# SS_24.net
KiCad netlist of a schematic drawn in Altium Designer
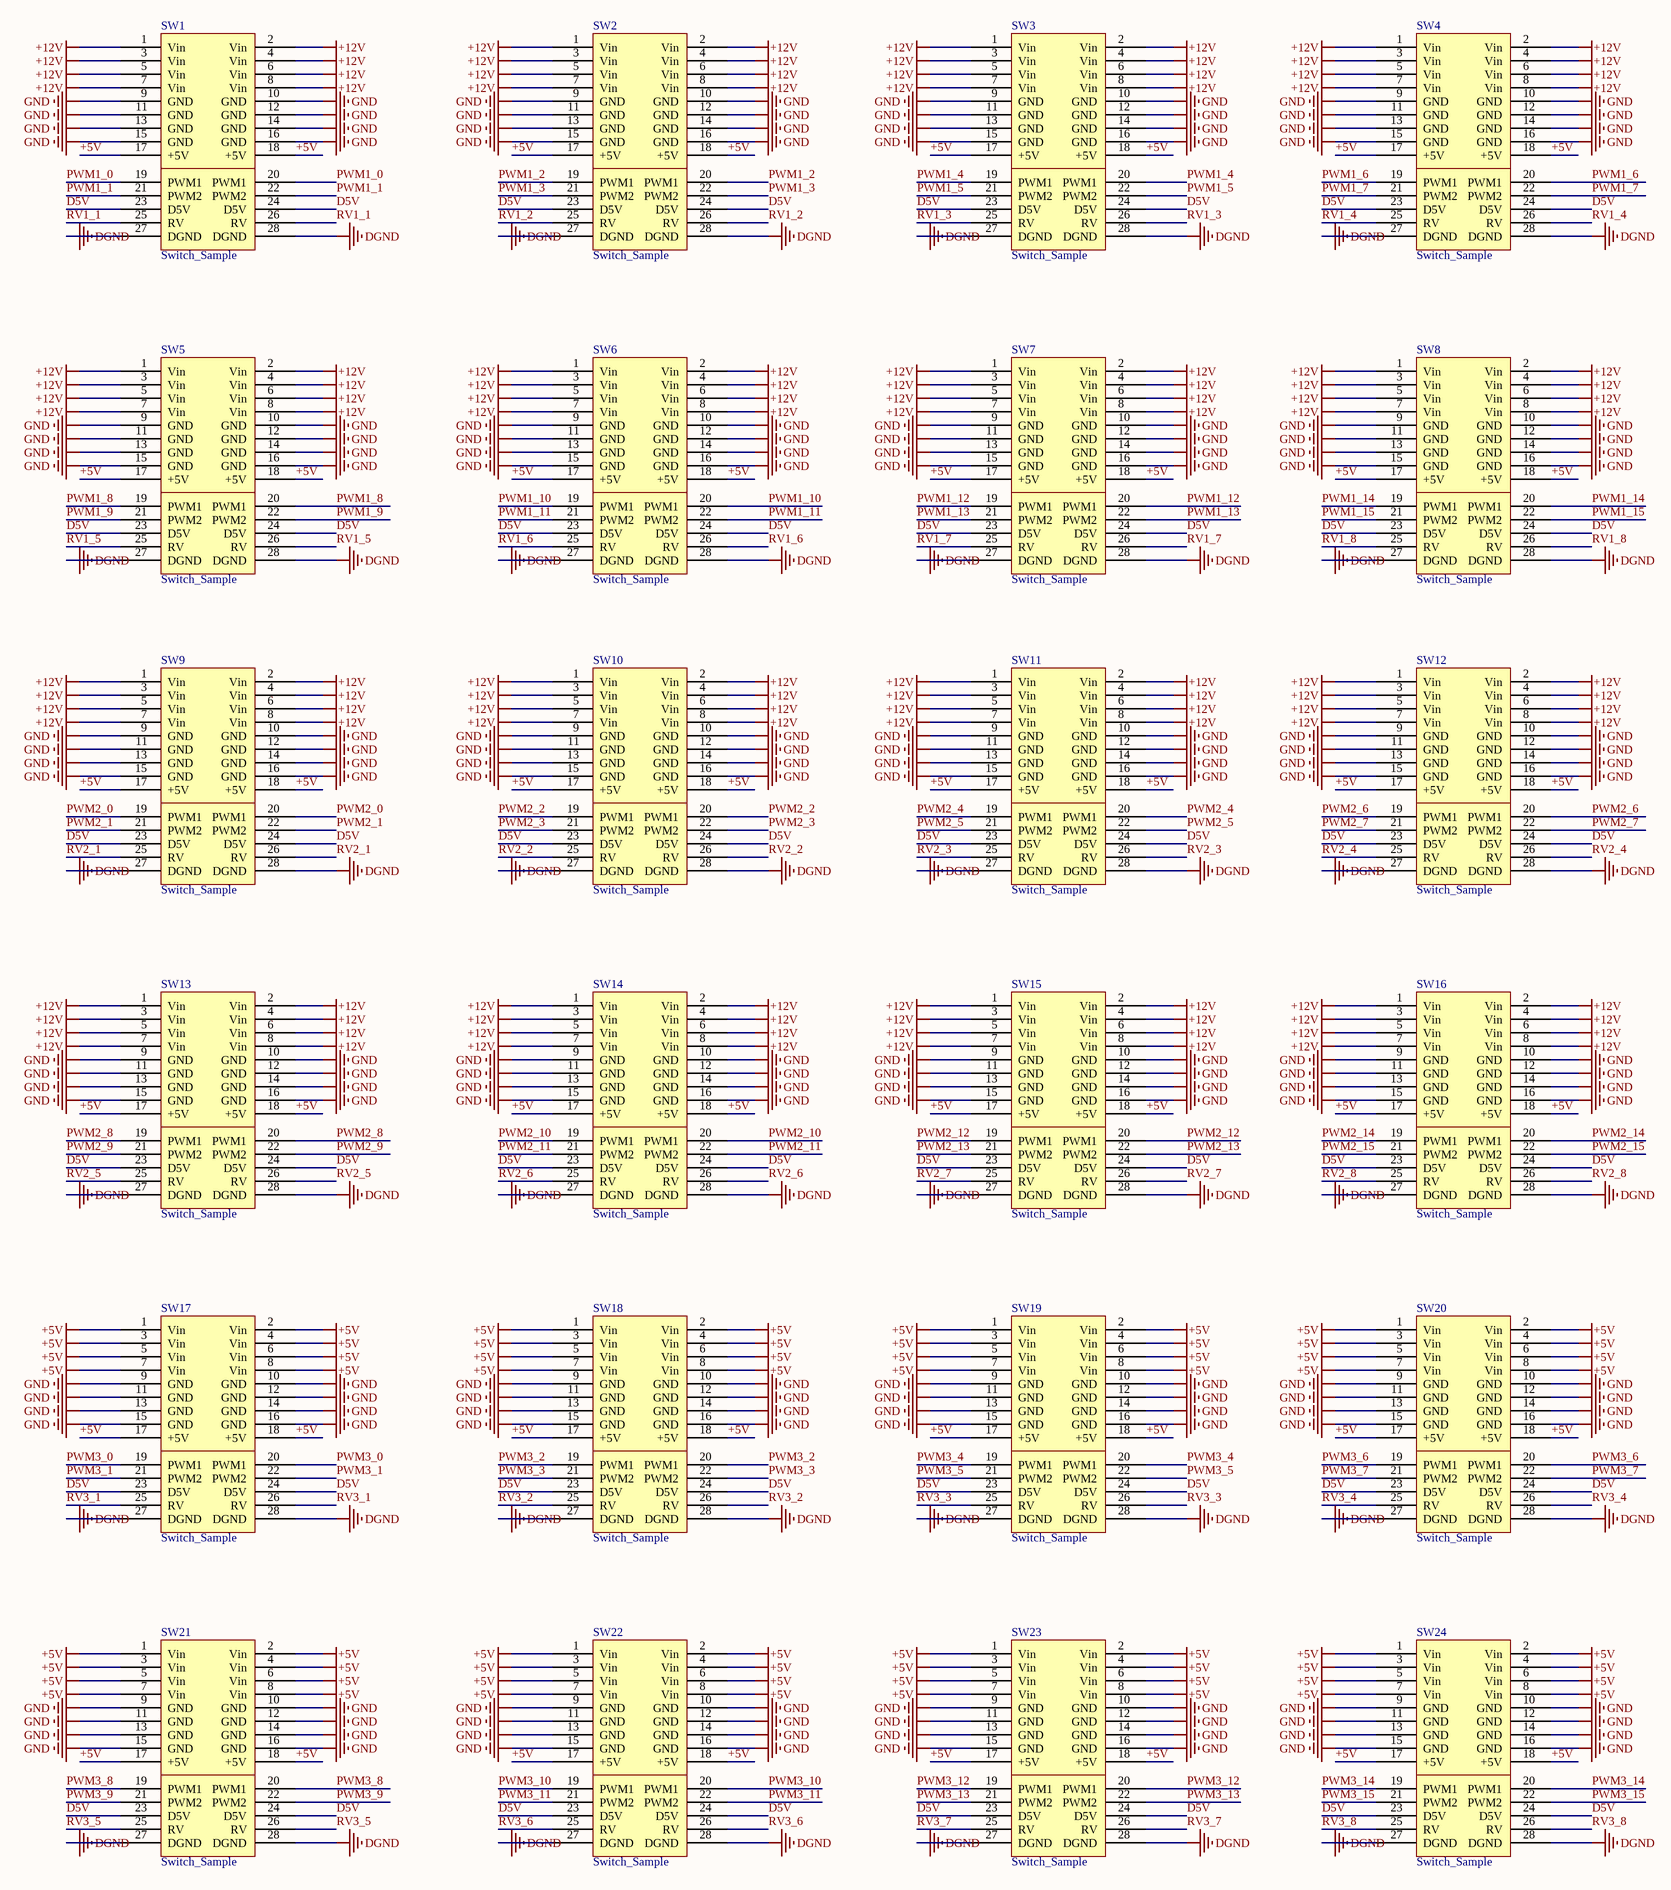
[diagram p0: SS_24.SchDoc]

(export (version "E")
  (design (tool "Eeschema 10.0.6"))
  (components
    (comp (ref "SW1")
      (value "Switch_Sample")
      (footprint "Switch_Sample")
      (libsource (lib "Schlib1") (part "Switch_Sample"))
    )
    (comp (ref "SW2")
      (value "Switch_Sample")
      (footprint "Switch_Sample")
      (libsource (lib "Schlib1") (part "Switch_Sample"))
    )
    (comp (ref "SW3")
      (value "Switch_Sample")
      (footprint "Switch_Sample")
      (libsource (lib "Schlib1") (part "Switch_Sample"))
    )
    (comp (ref "SW4")
      (value "Switch_Sample")
      (footprint "Switch_Sample")
      (libsource (lib "Schlib1") (part "Switch_Sample"))
    )
    (comp (ref "SW5")
      (value "Switch_Sample")
      (footprint "Switch_Sample")
      (libsource (lib "Schlib1") (part "Switch_Sample"))
    )
    (comp (ref "SW6")
      (value "Switch_Sample")
      (footprint "Switch_Sample")
      (libsource (lib "Schlib1") (part "Switch_Sample"))
    )
    (comp (ref "SW7")
      (value "Switch_Sample")
      (footprint "Switch_Sample")
      (libsource (lib "Schlib1") (part "Switch_Sample"))
    )
    (comp (ref "SW8")
      (value "Switch_Sample")
      (footprint "Switch_Sample")
      (libsource (lib "Schlib1") (part "Switch_Sample"))
    )
    (comp (ref "SW9")
      (value "Switch_Sample")
      (footprint "Switch_Sample")
      (libsource (lib "Schlib1") (part "Switch_Sample"))
    )
    (comp (ref "SW10")
      (value "Switch_Sample")
      (footprint "Switch_Sample")
      (libsource (lib "Schlib1") (part "Switch_Sample"))
    )
    (comp (ref "SW11")
      (value "Switch_Sample")
      (footprint "Switch_Sample")
      (libsource (lib "Schlib1") (part "Switch_Sample"))
    )
    (comp (ref "SW12")
      (value "Switch_Sample")
      (footprint "Switch_Sample")
      (libsource (lib "Schlib1") (part "Switch_Sample"))
    )
    (comp (ref "SW13")
      (value "Switch_Sample")
      (footprint "Switch_Sample")
      (libsource (lib "Schlib1") (part "Switch_Sample"))
    )
    (comp (ref "SW14")
      (value "Switch_Sample")
      (footprint "Switch_Sample")
      (libsource (lib "Schlib1") (part "Switch_Sample"))
    )
    (comp (ref "SW15")
      (value "Switch_Sample")
      (footprint "Switch_Sample")
      (libsource (lib "Schlib1") (part "Switch_Sample"))
    )
    (comp (ref "SW16")
      (value "Switch_Sample")
      (footprint "Switch_Sample")
      (libsource (lib "Schlib1") (part "Switch_Sample"))
    )
    (comp (ref "SW17")
      (value "Switch_Sample")
      (footprint "Switch_Sample")
      (libsource (lib "Schlib1") (part "Switch_Sample"))
    )
    (comp (ref "SW18")
      (value "Switch_Sample")
      (footprint "Switch_Sample")
      (libsource (lib "Schlib1") (part "Switch_Sample"))
    )
    (comp (ref "SW19")
      (value "Switch_Sample")
      (footprint "Switch_Sample")
      (libsource (lib "Schlib1") (part "Switch_Sample"))
    )
    (comp (ref "SW20")
      (value "Switch_Sample")
      (footprint "Switch_Sample")
      (libsource (lib "Schlib1") (part "Switch_Sample"))
    )
    (comp (ref "SW21")
      (value "Switch_Sample")
      (footprint "Switch_Sample")
      (libsource (lib "Schlib1") (part "Switch_Sample"))
    )
    (comp (ref "SW22")
      (value "Switch_Sample")
      (footprint "Switch_Sample")
      (libsource (lib "Schlib1") (part "Switch_Sample"))
    )
    (comp (ref "SW23")
      (value "Switch_Sample")
      (footprint "Switch_Sample")
      (libsource (lib "Schlib1") (part "Switch_Sample"))
    )
    (comp (ref "SW24")
      (value "Switch_Sample")
      (footprint "Switch_Sample")
      (libsource (lib "Schlib1") (part "Switch_Sample"))
    )
  )
  (nets
    (net (code "1") (name "+5V") (class "Default")
      (node (ref "SW1") (pin "17") (pinfunction "+5V_17") (pintype "passive"))
      (node (ref "SW1") (pin "18") (pinfunction "+5V_18") (pintype "passive"))
      (node (ref "SW10") (pin "17") (pinfunction "+5V_17") (pintype "passive"))
      (node (ref "SW10") (pin "18") (pinfunction "+5V_18") (pintype "passive"))
      (node (ref "SW11") (pin "17") (pinfunction "+5V_17") (pintype "passive"))
      (node (ref "SW11") (pin "18") (pinfunction "+5V_18") (pintype "passive"))
      (node (ref "SW12") (pin "17") (pinfunction "+5V_17") (pintype "passive"))
      (node (ref "SW12") (pin "18") (pinfunction "+5V_18") (pintype "passive"))
      (node (ref "SW13") (pin "17") (pinfunction "+5V_17") (pintype "passive"))
      (node (ref "SW13") (pin "18") (pinfunction "+5V_18") (pintype "passive"))
      (node (ref "SW14") (pin "17") (pinfunction "+5V_17") (pintype "passive"))
      (node (ref "SW14") (pin "18") (pinfunction "+5V_18") (pintype "passive"))
      (node (ref "SW15") (pin "17") (pinfunction "+5V_17") (pintype "passive"))
      (node (ref "SW15") (pin "18") (pinfunction "+5V_18") (pintype "passive"))
      (node (ref "SW16") (pin "17") (pinfunction "+5V_17") (pintype "passive"))
      (node (ref "SW16") (pin "18") (pinfunction "+5V_18") (pintype "passive"))
      (node (ref "SW17") (pin "1") (pinfunction "Vin_1") (pintype "passive"))
      (node (ref "SW17") (pin "17") (pinfunction "+5V_17") (pintype "passive"))
      (node (ref "SW17") (pin "18") (pinfunction "+5V_18") (pintype "passive"))
      (node (ref "SW17") (pin "2") (pinfunction "Vin_2") (pintype "passive"))
      (node (ref "SW17") (pin "3") (pinfunction "Vin_3") (pintype "passive"))
      (node (ref "SW17") (pin "4") (pinfunction "Vin_4") (pintype "passive"))
      (node (ref "SW17") (pin "5") (pinfunction "Vin_5") (pintype "passive"))
      (node (ref "SW17") (pin "6") (pinfunction "Vin_6") (pintype "passive"))
      (node (ref "SW17") (pin "7") (pinfunction "Vin_7") (pintype "passive"))
      (node (ref "SW17") (pin "8") (pinfunction "Vin_8") (pintype "passive"))
      (node (ref "SW18") (pin "1") (pinfunction "Vin_1") (pintype "passive"))
      (node (ref "SW18") (pin "17") (pinfunction "+5V_17") (pintype "passive"))
      (node (ref "SW18") (pin "18") (pinfunction "+5V_18") (pintype "passive"))
      (node (ref "SW18") (pin "2") (pinfunction "Vin_2") (pintype "passive"))
      (node (ref "SW18") (pin "3") (pinfunction "Vin_3") (pintype "passive"))
      (node (ref "SW18") (pin "4") (pinfunction "Vin_4") (pintype "passive"))
      (node (ref "SW18") (pin "5") (pinfunction "Vin_5") (pintype "passive"))
      (node (ref "SW18") (pin "6") (pinfunction "Vin_6") (pintype "passive"))
      (node (ref "SW18") (pin "7") (pinfunction "Vin_7") (pintype "passive"))
      (node (ref "SW18") (pin "8") (pinfunction "Vin_8") (pintype "passive"))
      (node (ref "SW19") (pin "1") (pinfunction "Vin_1") (pintype "passive"))
      (node (ref "SW19") (pin "17") (pinfunction "+5V_17") (pintype "passive"))
      (node (ref "SW19") (pin "18") (pinfunction "+5V_18") (pintype "passive"))
      (node (ref "SW19") (pin "2") (pinfunction "Vin_2") (pintype "passive"))
      (node (ref "SW19") (pin "3") (pinfunction "Vin_3") (pintype "passive"))
      (node (ref "SW19") (pin "4") (pinfunction "Vin_4") (pintype "passive"))
      (node (ref "SW19") (pin "5") (pinfunction "Vin_5") (pintype "passive"))
      (node (ref "SW19") (pin "6") (pinfunction "Vin_6") (pintype "passive"))
      (node (ref "SW19") (pin "7") (pinfunction "Vin_7") (pintype "passive"))
      (node (ref "SW19") (pin "8") (pinfunction "Vin_8") (pintype "passive"))
      (node (ref "SW2") (pin "17") (pinfunction "+5V_17") (pintype "passive"))
      (node (ref "SW2") (pin "18") (pinfunction "+5V_18") (pintype "passive"))
      (node (ref "SW20") (pin "1") (pinfunction "Vin_1") (pintype "passive"))
      (node (ref "SW20") (pin "17") (pinfunction "+5V_17") (pintype "passive"))
      (node (ref "SW20") (pin "18") (pinfunction "+5V_18") (pintype "passive"))
      (node (ref "SW20") (pin "2") (pinfunction "Vin_2") (pintype "passive"))
      (node (ref "SW20") (pin "3") (pinfunction "Vin_3") (pintype "passive"))
      (node (ref "SW20") (pin "4") (pinfunction "Vin_4") (pintype "passive"))
      (node (ref "SW20") (pin "5") (pinfunction "Vin_5") (pintype "passive"))
      (node (ref "SW20") (pin "6") (pinfunction "Vin_6") (pintype "passive"))
      (node (ref "SW20") (pin "7") (pinfunction "Vin_7") (pintype "passive"))
      (node (ref "SW20") (pin "8") (pinfunction "Vin_8") (pintype "passive"))
      (node (ref "SW21") (pin "1") (pinfunction "Vin_1") (pintype "passive"))
      (node (ref "SW21") (pin "17") (pinfunction "+5V_17") (pintype "passive"))
      (node (ref "SW21") (pin "18") (pinfunction "+5V_18") (pintype "passive"))
      (node (ref "SW21") (pin "2") (pinfunction "Vin_2") (pintype "passive"))
      (node (ref "SW21") (pin "3") (pinfunction "Vin_3") (pintype "passive"))
      (node (ref "SW21") (pin "4") (pinfunction "Vin_4") (pintype "passive"))
      (node (ref "SW21") (pin "5") (pinfunction "Vin_5") (pintype "passive"))
      (node (ref "SW21") (pin "6") (pinfunction "Vin_6") (pintype "passive"))
      (node (ref "SW21") (pin "7") (pinfunction "Vin_7") (pintype "passive"))
      (node (ref "SW21") (pin "8") (pinfunction "Vin_8") (pintype "passive"))
      (node (ref "SW22") (pin "1") (pinfunction "Vin_1") (pintype "passive"))
      (node (ref "SW22") (pin "17") (pinfunction "+5V_17") (pintype "passive"))
      (node (ref "SW22") (pin "18") (pinfunction "+5V_18") (pintype "passive"))
      (node (ref "SW22") (pin "2") (pinfunction "Vin_2") (pintype "passive"))
      (node (ref "SW22") (pin "3") (pinfunction "Vin_3") (pintype "passive"))
      (node (ref "SW22") (pin "4") (pinfunction "Vin_4") (pintype "passive"))
      (node (ref "SW22") (pin "5") (pinfunction "Vin_5") (pintype "passive"))
      (node (ref "SW22") (pin "6") (pinfunction "Vin_6") (pintype "passive"))
      (node (ref "SW22") (pin "7") (pinfunction "Vin_7") (pintype "passive"))
      (node (ref "SW22") (pin "8") (pinfunction "Vin_8") (pintype "passive"))
      (node (ref "SW23") (pin "1") (pinfunction "Vin_1") (pintype "passive"))
      (node (ref "SW23") (pin "17") (pinfunction "+5V_17") (pintype "passive"))
      (node (ref "SW23") (pin "18") (pinfunction "+5V_18") (pintype "passive"))
      (node (ref "SW23") (pin "2") (pinfunction "Vin_2") (pintype "passive"))
      (node (ref "SW23") (pin "3") (pinfunction "Vin_3") (pintype "passive"))
      (node (ref "SW23") (pin "4") (pinfunction "Vin_4") (pintype "passive"))
      (node (ref "SW23") (pin "5") (pinfunction "Vin_5") (pintype "passive"))
      (node (ref "SW23") (pin "6") (pinfunction "Vin_6") (pintype "passive"))
      (node (ref "SW23") (pin "7") (pinfunction "Vin_7") (pintype "passive"))
      (node (ref "SW23") (pin "8") (pinfunction "Vin_8") (pintype "passive"))
      (node (ref "SW24") (pin "1") (pinfunction "Vin_1") (pintype "passive"))
      (node (ref "SW24") (pin "17") (pinfunction "+5V_17") (pintype "passive"))
      (node (ref "SW24") (pin "18") (pinfunction "+5V_18") (pintype "passive"))
      (node (ref "SW24") (pin "2") (pinfunction "Vin_2") (pintype "passive"))
      (node (ref "SW24") (pin "3") (pinfunction "Vin_3") (pintype "passive"))
      (node (ref "SW24") (pin "4") (pinfunction "Vin_4") (pintype "passive"))
      (node (ref "SW24") (pin "5") (pinfunction "Vin_5") (pintype "passive"))
      (node (ref "SW24") (pin "6") (pinfunction "Vin_6") (pintype "passive"))
      (node (ref "SW24") (pin "7") (pinfunction "Vin_7") (pintype "passive"))
      (node (ref "SW24") (pin "8") (pinfunction "Vin_8") (pintype "passive"))
      (node (ref "SW3") (pin "17") (pinfunction "+5V_17") (pintype "passive"))
      (node (ref "SW3") (pin "18") (pinfunction "+5V_18") (pintype "passive"))
      (node (ref "SW4") (pin "17") (pinfunction "+5V_17") (pintype "passive"))
      (node (ref "SW4") (pin "18") (pinfunction "+5V_18") (pintype "passive"))
      (node (ref "SW5") (pin "17") (pinfunction "+5V_17") (pintype "passive"))
      (node (ref "SW5") (pin "18") (pinfunction "+5V_18") (pintype "passive"))
      (node (ref "SW6") (pin "17") (pinfunction "+5V_17") (pintype "passive"))
      (node (ref "SW6") (pin "18") (pinfunction "+5V_18") (pintype "passive"))
      (node (ref "SW7") (pin "17") (pinfunction "+5V_17") (pintype "passive"))
      (node (ref "SW7") (pin "18") (pinfunction "+5V_18") (pintype "passive"))
      (node (ref "SW8") (pin "17") (pinfunction "+5V_17") (pintype "passive"))
      (node (ref "SW8") (pin "18") (pinfunction "+5V_18") (pintype "passive"))
      (node (ref "SW9") (pin "17") (pinfunction "+5V_17") (pintype "passive"))
      (node (ref "SW9") (pin "18") (pinfunction "+5V_18") (pintype "passive"))
    )
    (net (code "2") (name "+12V") (class "Default")
      (node (ref "SW1") (pin "1") (pinfunction "Vin_1") (pintype "passive"))
      (node (ref "SW1") (pin "2") (pinfunction "Vin_2") (pintype "passive"))
      (node (ref "SW1") (pin "3") (pinfunction "Vin_3") (pintype "passive"))
      (node (ref "SW1") (pin "4") (pinfunction "Vin_4") (pintype "passive"))
      (node (ref "SW1") (pin "5") (pinfunction "Vin_5") (pintype "passive"))
      (node (ref "SW1") (pin "6") (pinfunction "Vin_6") (pintype "passive"))
      (node (ref "SW1") (pin "7") (pinfunction "Vin_7") (pintype "passive"))
      (node (ref "SW1") (pin "8") (pinfunction "Vin_8") (pintype "passive"))
      (node (ref "SW10") (pin "1") (pinfunction "Vin_1") (pintype "passive"))
      (node (ref "SW10") (pin "2") (pinfunction "Vin_2") (pintype "passive"))
      (node (ref "SW10") (pin "3") (pinfunction "Vin_3") (pintype "passive"))
      (node (ref "SW10") (pin "4") (pinfunction "Vin_4") (pintype "passive"))
      (node (ref "SW10") (pin "5") (pinfunction "Vin_5") (pintype "passive"))
      (node (ref "SW10") (pin "6") (pinfunction "Vin_6") (pintype "passive"))
      (node (ref "SW10") (pin "7") (pinfunction "Vin_7") (pintype "passive"))
      (node (ref "SW10") (pin "8") (pinfunction "Vin_8") (pintype "passive"))
      (node (ref "SW11") (pin "1") (pinfunction "Vin_1") (pintype "passive"))
      (node (ref "SW11") (pin "2") (pinfunction "Vin_2") (pintype "passive"))
      (node (ref "SW11") (pin "3") (pinfunction "Vin_3") (pintype "passive"))
      (node (ref "SW11") (pin "4") (pinfunction "Vin_4") (pintype "passive"))
      (node (ref "SW11") (pin "5") (pinfunction "Vin_5") (pintype "passive"))
      (node (ref "SW11") (pin "6") (pinfunction "Vin_6") (pintype "passive"))
      (node (ref "SW11") (pin "7") (pinfunction "Vin_7") (pintype "passive"))
      (node (ref "SW11") (pin "8") (pinfunction "Vin_8") (pintype "passive"))
      (node (ref "SW12") (pin "1") (pinfunction "Vin_1") (pintype "passive"))
      (node (ref "SW12") (pin "2") (pinfunction "Vin_2") (pintype "passive"))
      (node (ref "SW12") (pin "3") (pinfunction "Vin_3") (pintype "passive"))
      (node (ref "SW12") (pin "4") (pinfunction "Vin_4") (pintype "passive"))
      (node (ref "SW12") (pin "5") (pinfunction "Vin_5") (pintype "passive"))
      (node (ref "SW12") (pin "6") (pinfunction "Vin_6") (pintype "passive"))
      (node (ref "SW12") (pin "7") (pinfunction "Vin_7") (pintype "passive"))
      (node (ref "SW12") (pin "8") (pinfunction "Vin_8") (pintype "passive"))
      (node (ref "SW13") (pin "1") (pinfunction "Vin_1") (pintype "passive"))
      (node (ref "SW13") (pin "2") (pinfunction "Vin_2") (pintype "passive"))
      (node (ref "SW13") (pin "3") (pinfunction "Vin_3") (pintype "passive"))
      (node (ref "SW13") (pin "4") (pinfunction "Vin_4") (pintype "passive"))
      (node (ref "SW13") (pin "5") (pinfunction "Vin_5") (pintype "passive"))
      (node (ref "SW13") (pin "6") (pinfunction "Vin_6") (pintype "passive"))
      (node (ref "SW13") (pin "7") (pinfunction "Vin_7") (pintype "passive"))
      (node (ref "SW13") (pin "8") (pinfunction "Vin_8") (pintype "passive"))
      (node (ref "SW14") (pin "1") (pinfunction "Vin_1") (pintype "passive"))
      (node (ref "SW14") (pin "2") (pinfunction "Vin_2") (pintype "passive"))
      (node (ref "SW14") (pin "3") (pinfunction "Vin_3") (pintype "passive"))
      (node (ref "SW14") (pin "4") (pinfunction "Vin_4") (pintype "passive"))
      (node (ref "SW14") (pin "5") (pinfunction "Vin_5") (pintype "passive"))
      (node (ref "SW14") (pin "6") (pinfunction "Vin_6") (pintype "passive"))
      (node (ref "SW14") (pin "7") (pinfunction "Vin_7") (pintype "passive"))
      (node (ref "SW14") (pin "8") (pinfunction "Vin_8") (pintype "passive"))
      (node (ref "SW15") (pin "1") (pinfunction "Vin_1") (pintype "passive"))
      (node (ref "SW15") (pin "2") (pinfunction "Vin_2") (pintype "passive"))
      (node (ref "SW15") (pin "3") (pinfunction "Vin_3") (pintype "passive"))
      (node (ref "SW15") (pin "4") (pinfunction "Vin_4") (pintype "passive"))
      (node (ref "SW15") (pin "5") (pinfunction "Vin_5") (pintype "passive"))
      (node (ref "SW15") (pin "6") (pinfunction "Vin_6") (pintype "passive"))
      (node (ref "SW15") (pin "7") (pinfunction "Vin_7") (pintype "passive"))
      (node (ref "SW15") (pin "8") (pinfunction "Vin_8") (pintype "passive"))
      (node (ref "SW16") (pin "1") (pinfunction "Vin_1") (pintype "passive"))
      (node (ref "SW16") (pin "2") (pinfunction "Vin_2") (pintype "passive"))
      (node (ref "SW16") (pin "3") (pinfunction "Vin_3") (pintype "passive"))
      (node (ref "SW16") (pin "4") (pinfunction "Vin_4") (pintype "passive"))
      (node (ref "SW16") (pin "5") (pinfunction "Vin_5") (pintype "passive"))
      (node (ref "SW16") (pin "6") (pinfunction "Vin_6") (pintype "passive"))
      (node (ref "SW16") (pin "7") (pinfunction "Vin_7") (pintype "passive"))
      (node (ref "SW16") (pin "8") (pinfunction "Vin_8") (pintype "passive"))
      (node (ref "SW2") (pin "1") (pinfunction "Vin_1") (pintype "passive"))
      (node (ref "SW2") (pin "2") (pinfunction "Vin_2") (pintype "passive"))
      (node (ref "SW2") (pin "3") (pinfunction "Vin_3") (pintype "passive"))
      (node (ref "SW2") (pin "4") (pinfunction "Vin_4") (pintype "passive"))
      (node (ref "SW2") (pin "5") (pinfunction "Vin_5") (pintype "passive"))
      (node (ref "SW2") (pin "6") (pinfunction "Vin_6") (pintype "passive"))
      (node (ref "SW2") (pin "7") (pinfunction "Vin_7") (pintype "passive"))
      (node (ref "SW2") (pin "8") (pinfunction "Vin_8") (pintype "passive"))
      (node (ref "SW3") (pin "1") (pinfunction "Vin_1") (pintype "passive"))
      (node (ref "SW3") (pin "2") (pinfunction "Vin_2") (pintype "passive"))
      (node (ref "SW3") (pin "3") (pinfunction "Vin_3") (pintype "passive"))
      (node (ref "SW3") (pin "4") (pinfunction "Vin_4") (pintype "passive"))
      (node (ref "SW3") (pin "5") (pinfunction "Vin_5") (pintype "passive"))
      (node (ref "SW3") (pin "6") (pinfunction "Vin_6") (pintype "passive"))
      (node (ref "SW3") (pin "7") (pinfunction "Vin_7") (pintype "passive"))
      (node (ref "SW3") (pin "8") (pinfunction "Vin_8") (pintype "passive"))
      (node (ref "SW4") (pin "1") (pinfunction "Vin_1") (pintype "passive"))
      (node (ref "SW4") (pin "2") (pinfunction "Vin_2") (pintype "passive"))
      (node (ref "SW4") (pin "3") (pinfunction "Vin_3") (pintype "passive"))
      (node (ref "SW4") (pin "4") (pinfunction "Vin_4") (pintype "passive"))
      (node (ref "SW4") (pin "5") (pinfunction "Vin_5") (pintype "passive"))
      (node (ref "SW4") (pin "6") (pinfunction "Vin_6") (pintype "passive"))
      (node (ref "SW4") (pin "7") (pinfunction "Vin_7") (pintype "passive"))
      (node (ref "SW4") (pin "8") (pinfunction "Vin_8") (pintype "passive"))
      (node (ref "SW5") (pin "1") (pinfunction "Vin_1") (pintype "passive"))
      (node (ref "SW5") (pin "2") (pinfunction "Vin_2") (pintype "passive"))
      (node (ref "SW5") (pin "3") (pinfunction "Vin_3") (pintype "passive"))
      (node (ref "SW5") (pin "4") (pinfunction "Vin_4") (pintype "passive"))
      (node (ref "SW5") (pin "5") (pinfunction "Vin_5") (pintype "passive"))
      (node (ref "SW5") (pin "6") (pinfunction "Vin_6") (pintype "passive"))
      (node (ref "SW5") (pin "7") (pinfunction "Vin_7") (pintype "passive"))
      (node (ref "SW5") (pin "8") (pinfunction "Vin_8") (pintype "passive"))
      (node (ref "SW6") (pin "1") (pinfunction "Vin_1") (pintype "passive"))
      (node (ref "SW6") (pin "2") (pinfunction "Vin_2") (pintype "passive"))
      (node (ref "SW6") (pin "3") (pinfunction "Vin_3") (pintype "passive"))
      (node (ref "SW6") (pin "4") (pinfunction "Vin_4") (pintype "passive"))
      (node (ref "SW6") (pin "5") (pinfunction "Vin_5") (pintype "passive"))
      (node (ref "SW6") (pin "6") (pinfunction "Vin_6") (pintype "passive"))
      (node (ref "SW6") (pin "7") (pinfunction "Vin_7") (pintype "passive"))
      (node (ref "SW6") (pin "8") (pinfunction "Vin_8") (pintype "passive"))
      (node (ref "SW7") (pin "1") (pinfunction "Vin_1") (pintype "passive"))
      (node (ref "SW7") (pin "2") (pinfunction "Vin_2") (pintype "passive"))
      (node (ref "SW7") (pin "3") (pinfunction "Vin_3") (pintype "passive"))
      (node (ref "SW7") (pin "4") (pinfunction "Vin_4") (pintype "passive"))
      (node (ref "SW7") (pin "5") (pinfunction "Vin_5") (pintype "passive"))
      (node (ref "SW7") (pin "6") (pinfunction "Vin_6") (pintype "passive"))
      (node (ref "SW7") (pin "7") (pinfunction "Vin_7") (pintype "passive"))
      (node (ref "SW7") (pin "8") (pinfunction "Vin_8") (pintype "passive"))
      (node (ref "SW8") (pin "1") (pinfunction "Vin_1") (pintype "passive"))
      (node (ref "SW8") (pin "2") (pinfunction "Vin_2") (pintype "passive"))
      (node (ref "SW8") (pin "3") (pinfunction "Vin_3") (pintype "passive"))
      (node (ref "SW8") (pin "4") (pinfunction "Vin_4") (pintype "passive"))
      (node (ref "SW8") (pin "5") (pinfunction "Vin_5") (pintype "passive"))
      (node (ref "SW8") (pin "6") (pinfunction "Vin_6") (pintype "passive"))
      (node (ref "SW8") (pin "7") (pinfunction "Vin_7") (pintype "passive"))
      (node (ref "SW8") (pin "8") (pinfunction "Vin_8") (pintype "passive"))
      (node (ref "SW9") (pin "1") (pinfunction "Vin_1") (pintype "passive"))
      (node (ref "SW9") (pin "2") (pinfunction "Vin_2") (pintype "passive"))
      (node (ref "SW9") (pin "3") (pinfunction "Vin_3") (pintype "passive"))
      (node (ref "SW9") (pin "4") (pinfunction "Vin_4") (pintype "passive"))
      (node (ref "SW9") (pin "5") (pinfunction "Vin_5") (pintype "passive"))
      (node (ref "SW9") (pin "6") (pinfunction "Vin_6") (pintype "passive"))
      (node (ref "SW9") (pin "7") (pinfunction "Vin_7") (pintype "passive"))
      (node (ref "SW9") (pin "8") (pinfunction "Vin_8") (pintype "passive"))
    )
    (net (code "3") (name "/D5V") (class "Default")
      (node (ref "SW1") (pin "23") (pinfunction "D5V_23") (pintype "passive"))
      (node (ref "SW1") (pin "24") (pinfunction "D5V_24") (pintype "passive"))
      (node (ref "SW10") (pin "23") (pinfunction "D5V_23") (pintype "passive"))
      (node (ref "SW10") (pin "24") (pinfunction "D5V_24") (pintype "passive"))
      (node (ref "SW11") (pin "23") (pinfunction "D5V_23") (pintype "passive"))
      (node (ref "SW11") (pin "24") (pinfunction "D5V_24") (pintype "passive"))
      (node (ref "SW12") (pin "23") (pinfunction "D5V_23") (pintype "passive"))
      (node (ref "SW12") (pin "24") (pinfunction "D5V_24") (pintype "passive"))
      (node (ref "SW13") (pin "23") (pinfunction "D5V_23") (pintype "passive"))
      (node (ref "SW13") (pin "24") (pinfunction "D5V_24") (pintype "passive"))
      (node (ref "SW14") (pin "23") (pinfunction "D5V_23") (pintype "passive"))
      (node (ref "SW14") (pin "24") (pinfunction "D5V_24") (pintype "passive"))
      (node (ref "SW15") (pin "23") (pinfunction "D5V_23") (pintype "passive"))
      (node (ref "SW15") (pin "24") (pinfunction "D5V_24") (pintype "passive"))
      (node (ref "SW16") (pin "23") (pinfunction "D5V_23") (pintype "passive"))
      (node (ref "SW16") (pin "24") (pinfunction "D5V_24") (pintype "passive"))
      (node (ref "SW17") (pin "23") (pinfunction "D5V_23") (pintype "passive"))
      (node (ref "SW17") (pin "24") (pinfunction "D5V_24") (pintype "passive"))
      (node (ref "SW18") (pin "23") (pinfunction "D5V_23") (pintype "passive"))
      (node (ref "SW18") (pin "24") (pinfunction "D5V_24") (pintype "passive"))
      (node (ref "SW19") (pin "23") (pinfunction "D5V_23") (pintype "passive"))
      (node (ref "SW19") (pin "24") (pinfunction "D5V_24") (pintype "passive"))
      (node (ref "SW2") (pin "23") (pinfunction "D5V_23") (pintype "passive"))
      (node (ref "SW2") (pin "24") (pinfunction "D5V_24") (pintype "passive"))
      (node (ref "SW20") (pin "23") (pinfunction "D5V_23") (pintype "passive"))
      (node (ref "SW20") (pin "24") (pinfunction "D5V_24") (pintype "passive"))
      (node (ref "SW21") (pin "23") (pinfunction "D5V_23") (pintype "passive"))
      (node (ref "SW21") (pin "24") (pinfunction "D5V_24") (pintype "passive"))
      (node (ref "SW22") (pin "23") (pinfunction "D5V_23") (pintype "passive"))
      (node (ref "SW22") (pin "24") (pinfunction "D5V_24") (pintype "passive"))
      (node (ref "SW23") (pin "23") (pinfunction "D5V_23") (pintype "passive"))
      (node (ref "SW23") (pin "24") (pinfunction "D5V_24") (pintype "passive"))
      (node (ref "SW24") (pin "23") (pinfunction "D5V_23") (pintype "passive"))
      (node (ref "SW24") (pin "24") (pinfunction "D5V_24") (pintype "passive"))
      (node (ref "SW3") (pin "23") (pinfunction "D5V_23") (pintype "passive"))
      (node (ref "SW3") (pin "24") (pinfunction "D5V_24") (pintype "passive"))
      (node (ref "SW4") (pin "23") (pinfunction "D5V_23") (pintype "passive"))
      (node (ref "SW4") (pin "24") (pinfunction "D5V_24") (pintype "passive"))
      (node (ref "SW5") (pin "23") (pinfunction "D5V_23") (pintype "passive"))
      (node (ref "SW5") (pin "24") (pinfunction "D5V_24") (pintype "passive"))
      (node (ref "SW6") (pin "23") (pinfunction "D5V_23") (pintype "passive"))
      (node (ref "SW6") (pin "24") (pinfunction "D5V_24") (pintype "passive"))
      (node (ref "SW7") (pin "23") (pinfunction "D5V_23") (pintype "passive"))
      (node (ref "SW7") (pin "24") (pinfunction "D5V_24") (pintype "passive"))
      (node (ref "SW8") (pin "23") (pinfunction "D5V_23") (pintype "passive"))
      (node (ref "SW8") (pin "24") (pinfunction "D5V_24") (pintype "passive"))
      (node (ref "SW9") (pin "23") (pinfunction "D5V_23") (pintype "passive"))
      (node (ref "SW9") (pin "24") (pinfunction "D5V_24") (pintype "passive"))
    )
    (net (code "4") (name "/PWM1_0") (class "Default")
      (node (ref "SW1") (pin "19") (pinfunction "PWM1_19") (pintype "passive"))
      (node (ref "SW1") (pin "20") (pinfunction "PWM1_20") (pintype "passive"))
    )
    (net (code "5") (name "/PWM1_1") (class "Default")
      (node (ref "SW1") (pin "21") (pinfunction "PWM2_21") (pintype "passive"))
      (node (ref "SW1") (pin "22") (pinfunction "PWM2_22") (pintype "passive"))
    )
    (net (code "6") (name "/PWM1_2") (class "Default")
      (node (ref "SW2") (pin "19") (pinfunction "PWM1_19") (pintype "passive"))
      (node (ref "SW2") (pin "20") (pinfunction "PWM1_20") (pintype "passive"))
    )
    (net (code "7") (name "/PWM1_3") (class "Default")
      (node (ref "SW2") (pin "21") (pinfunction "PWM2_21") (pintype "passive"))
      (node (ref "SW2") (pin "22") (pinfunction "PWM2_22") (pintype "passive"))
    )
    (net (code "8") (name "/PWM1_4") (class "Default")
      (node (ref "SW3") (pin "19") (pinfunction "PWM1_19") (pintype "passive"))
      (node (ref "SW3") (pin "20") (pinfunction "PWM1_20") (pintype "passive"))
    )
    (net (code "9") (name "/PWM1_5") (class "Default")
      (node (ref "SW3") (pin "21") (pinfunction "PWM2_21") (pintype "passive"))
      (node (ref "SW3") (pin "22") (pinfunction "PWM2_22") (pintype "passive"))
    )
    (net (code "10") (name "/PWM1_6") (class "Default")
      (node (ref "SW4") (pin "19") (pinfunction "PWM1_19") (pintype "passive"))
      (node (ref "SW4") (pin "20") (pinfunction "PWM1_20") (pintype "passive"))
    )
    (net (code "11") (name "/PWM1_7") (class "Default")
      (node (ref "SW4") (pin "21") (pinfunction "PWM2_21") (pintype "passive"))
      (node (ref "SW4") (pin "22") (pinfunction "PWM2_22") (pintype "passive"))
    )
    (net (code "12") (name "/PWM1_8") (class "Default")
      (node (ref "SW5") (pin "19") (pinfunction "PWM1_19") (pintype "passive"))
      (node (ref "SW5") (pin "20") (pinfunction "PWM1_20") (pintype "passive"))
    )
    (net (code "13") (name "/PWM1_9") (class "Default")
      (node (ref "SW5") (pin "21") (pinfunction "PWM2_21") (pintype "passive"))
      (node (ref "SW5") (pin "22") (pinfunction "PWM2_22") (pintype "passive"))
    )
    (net (code "14") (name "/PWM1_10") (class "Default")
      (node (ref "SW6") (pin "19") (pinfunction "PWM1_19") (pintype "passive"))
      (node (ref "SW6") (pin "20") (pinfunction "PWM1_20") (pintype "passive"))
    )
    (net (code "15") (name "/PWM1_11") (class "Default")
      (node (ref "SW6") (pin "21") (pinfunction "PWM2_21") (pintype "passive"))
      (node (ref "SW6") (pin "22") (pinfunction "PWM2_22") (pintype "passive"))
    )
    (net (code "16") (name "/PWM1_12") (class "Default")
      (node (ref "SW7") (pin "19") (pinfunction "PWM1_19") (pintype "passive"))
      (node (ref "SW7") (pin "20") (pinfunction "PWM1_20") (pintype "passive"))
    )
    (net (code "17") (name "/PWM1_13") (class "Default")
      (node (ref "SW7") (pin "21") (pinfunction "PWM2_21") (pintype "passive"))
      (node (ref "SW7") (pin "22") (pinfunction "PWM2_22") (pintype "passive"))
    )
    (net (code "18") (name "/PWM1_14") (class "Default")
      (node (ref "SW8") (pin "19") (pinfunction "PWM1_19") (pintype "passive"))
      (node (ref "SW8") (pin "20") (pinfunction "PWM1_20") (pintype "passive"))
    )
    (net (code "19") (name "/PWM1_15") (class "Default")
      (node (ref "SW8") (pin "21") (pinfunction "PWM2_21") (pintype "passive"))
      (node (ref "SW8") (pin "22") (pinfunction "PWM2_22") (pintype "passive"))
    )
    (net (code "20") (name "/PWM2_0") (class "Default")
      (node (ref "SW9") (pin "19") (pinfunction "PWM1_19") (pintype "passive"))
      (node (ref "SW9") (pin "20") (pinfunction "PWM1_20") (pintype "passive"))
    )
    (net (code "21") (name "/PWM2_1") (class "Default")
      (node (ref "SW9") (pin "21") (pinfunction "PWM2_21") (pintype "passive"))
      (node (ref "SW9") (pin "22") (pinfunction "PWM2_22") (pintype "passive"))
    )
    (net (code "22") (name "/PWM2_2") (class "Default")
      (node (ref "SW10") (pin "19") (pinfunction "PWM1_19") (pintype "passive"))
      (node (ref "SW10") (pin "20") (pinfunction "PWM1_20") (pintype "passive"))
    )
    (net (code "23") (name "/PWM2_3") (class "Default")
      (node (ref "SW10") (pin "21") (pinfunction "PWM2_21") (pintype "passive"))
      (node (ref "SW10") (pin "22") (pinfunction "PWM2_22") (pintype "passive"))
    )
    (net (code "24") (name "/PWM2_4") (class "Default")
      (node (ref "SW11") (pin "19") (pinfunction "PWM1_19") (pintype "passive"))
      (node (ref "SW11") (pin "20") (pinfunction "PWM1_20") (pintype "passive"))
    )
    (net (code "25") (name "/PWM2_5") (class "Default")
      (node (ref "SW11") (pin "21") (pinfunction "PWM2_21") (pintype "passive"))
      (node (ref "SW11") (pin "22") (pinfunction "PWM2_22") (pintype "passive"))
    )
    (net (code "26") (name "/PWM2_6") (class "Default")
      (node (ref "SW12") (pin "19") (pinfunction "PWM1_19") (pintype "passive"))
      (node (ref "SW12") (pin "20") (pinfunction "PWM1_20") (pintype "passive"))
    )
    (net (code "27") (name "/PWM2_7") (class "Default")
      (node (ref "SW12") (pin "21") (pinfunction "PWM2_21") (pintype "passive"))
      (node (ref "SW12") (pin "22") (pinfunction "PWM2_22") (pintype "passive"))
    )
    (net (code "28") (name "/PWM2_8") (class "Default")
      (node (ref "SW13") (pin "19") (pinfunction "PWM1_19") (pintype "passive"))
      (node (ref "SW13") (pin "20") (pinfunction "PWM1_20") (pintype "passive"))
    )
    (net (code "29") (name "/PWM2_9") (class "Default")
      (node (ref "SW13") (pin "21") (pinfunction "PWM2_21") (pintype "passive"))
      (node (ref "SW13") (pin "22") (pinfunction "PWM2_22") (pintype "passive"))
    )
    (net (code "30") (name "/PWM2_10") (class "Default")
      (node (ref "SW14") (pin "19") (pinfunction "PWM1_19") (pintype "passive"))
      (node (ref "SW14") (pin "20") (pinfunction "PWM1_20") (pintype "passive"))
    )
    (net (code "31") (name "/PWM2_11") (class "Default")
      (node (ref "SW14") (pin "21") (pinfunction "PWM2_21") (pintype "passive"))
      (node (ref "SW14") (pin "22") (pinfunction "PWM2_22") (pintype "passive"))
    )
    (net (code "32") (name "/PWM2_12") (class "Default")
      (node (ref "SW15") (pin "19") (pinfunction "PWM1_19") (pintype "passive"))
      (node (ref "SW15") (pin "20") (pinfunction "PWM1_20") (pintype "passive"))
    )
    (net (code "33") (name "/PWM2_13") (class "Default")
      (node (ref "SW15") (pin "21") (pinfunction "PWM2_21") (pintype "passive"))
      (node (ref "SW15") (pin "22") (pinfunction "PWM2_22") (pintype "passive"))
    )
    (net (code "34") (name "/PWM2_14") (class "Default")
      (node (ref "SW16") (pin "19") (pinfunction "PWM1_19") (pintype "passive"))
      (node (ref "SW16") (pin "20") (pinfunction "PWM1_20") (pintype "passive"))
    )
    (net (code "35") (name "/PWM2_15") (class "Default")
      (node (ref "SW16") (pin "21") (pinfunction "PWM2_21") (pintype "passive"))
      (node (ref "SW16") (pin "22") (pinfunction "PWM2_22") (pintype "passive"))
    )
    (net (code "36") (name "/PWM3_0") (class "Default")
      (node (ref "SW17") (pin "19") (pinfunction "PWM1_19") (pintype "passive"))
      (node (ref "SW17") (pin "20") (pinfunction "PWM1_20") (pintype "passive"))
    )
    (net (code "37") (name "/PWM3_1") (class "Default")
      (node (ref "SW17") (pin "21") (pinfunction "PWM2_21") (pintype "passive"))
      (node (ref "SW17") (pin "22") (pinfunction "PWM2_22") (pintype "passive"))
    )
    (net (code "38") (name "/PWM3_2") (class "Default")
      (node (ref "SW18") (pin "19") (pinfunction "PWM1_19") (pintype "passive"))
      (node (ref "SW18") (pin "20") (pinfunction "PWM1_20") (pintype "passive"))
    )
    (net (code "39") (name "/PWM3_3") (class "Default")
      (node (ref "SW18") (pin "21") (pinfunction "PWM2_21") (pintype "passive"))
      (node (ref "SW18") (pin "22") (pinfunction "PWM2_22") (pintype "passive"))
    )
    (net (code "40") (name "/PWM3_4") (class "Default")
      (node (ref "SW19") (pin "19") (pinfunction "PWM1_19") (pintype "passive"))
      (node (ref "SW19") (pin "20") (pinfunction "PWM1_20") (pintype "passive"))
    )
    (net (code "41") (name "/PWM3_5") (class "Default")
      (node (ref "SW19") (pin "21") (pinfunction "PWM2_21") (pintype "passive"))
      (node (ref "SW19") (pin "22") (pinfunction "PWM2_22") (pintype "passive"))
    )
    (net (code "42") (name "/PWM3_6") (class "Default")
      (node (ref "SW20") (pin "19") (pinfunction "PWM1_19") (pintype "passive"))
      (node (ref "SW20") (pin "20") (pinfunction "PWM1_20") (pintype "passive"))
    )
    (net (code "43") (name "/PWM3_7") (class "Default")
      (node (ref "SW20") (pin "21") (pinfunction "PWM2_21") (pintype "passive"))
      (node (ref "SW20") (pin "22") (pinfunction "PWM2_22") (pintype "passive"))
    )
    (net (code "44") (name "/PWM3_8") (class "Default")
      (node (ref "SW21") (pin "19") (pinfunction "PWM1_19") (pintype "passive"))
      (node (ref "SW21") (pin "20") (pinfunction "PWM1_20") (pintype "passive"))
    )
    (net (code "45") (name "/PWM3_9") (class "Default")
      (node (ref "SW21") (pin "21") (pinfunction "PWM2_21") (pintype "passive"))
      (node (ref "SW21") (pin "22") (pinfunction "PWM2_22") (pintype "passive"))
    )
    (net (code "46") (name "/PWM3_10") (class "Default")
      (node (ref "SW22") (pin "19") (pinfunction "PWM1_19") (pintype "passive"))
      (node (ref "SW22") (pin "20") (pinfunction "PWM1_20") (pintype "passive"))
    )
    (net (code "47") (name "/PWM3_11") (class "Default")
      (node (ref "SW22") (pin "21") (pinfunction "PWM2_21") (pintype "passive"))
      (node (ref "SW22") (pin "22") (pinfunction "PWM2_22") (pintype "passive"))
    )
    (net (code "48") (name "/PWM3_12") (class "Default")
      (node (ref "SW23") (pin "19") (pinfunction "PWM1_19") (pintype "passive"))
      (node (ref "SW23") (pin "20") (pinfunction "PWM1_20") (pintype "passive"))
    )
    (net (code "49") (name "/PWM3_13") (class "Default")
      (node (ref "SW23") (pin "21") (pinfunction "PWM2_21") (pintype "passive"))
      (node (ref "SW23") (pin "22") (pinfunction "PWM2_22") (pintype "passive"))
    )
    (net (code "50") (name "/PWM3_14") (class "Default")
      (node (ref "SW24") (pin "19") (pinfunction "PWM1_19") (pintype "passive"))
      (node (ref "SW24") (pin "20") (pinfunction "PWM1_20") (pintype "passive"))
    )
    (net (code "51") (name "/PWM3_15") (class "Default")
      (node (ref "SW24") (pin "21") (pinfunction "PWM2_21") (pintype "passive"))
      (node (ref "SW24") (pin "22") (pinfunction "PWM2_22") (pintype "passive"))
    )
    (net (code "52") (name "/RV1_1") (class "Default")
      (node (ref "SW1") (pin "25") (pinfunction "RV_25") (pintype "passive"))
      (node (ref "SW1") (pin "26") (pinfunction "RV_26") (pintype "passive"))
    )
    (net (code "53") (name "/RV1_2") (class "Default")
      (node (ref "SW2") (pin "25") (pinfunction "RV_25") (pintype "passive"))
      (node (ref "SW2") (pin "26") (pinfunction "RV_26") (pintype "passive"))
    )
    (net (code "54") (name "/RV1_3") (class "Default")
      (node (ref "SW3") (pin "25") (pinfunction "RV_25") (pintype "passive"))
      (node (ref "SW3") (pin "26") (pinfunction "RV_26") (pintype "passive"))
    )
    (net (code "55") (name "/RV1_4") (class "Default")
      (node (ref "SW4") (pin "25") (pinfunction "RV_25") (pintype "passive"))
      (node (ref "SW4") (pin "26") (pinfunction "RV_26") (pintype "passive"))
    )
    (net (code "56") (name "/RV1_5") (class "Default")
      (node (ref "SW5") (pin "25") (pinfunction "RV_25") (pintype "passive"))
      (node (ref "SW5") (pin "26") (pinfunction "RV_26") (pintype "passive"))
    )
    (net (code "57") (name "/RV1_6") (class "Default")
      (node (ref "SW6") (pin "25") (pinfunction "RV_25") (pintype "passive"))
      (node (ref "SW6") (pin "26") (pinfunction "RV_26") (pintype "passive"))
    )
    (net (code "58") (name "/RV1_7") (class "Default")
      (node (ref "SW7") (pin "25") (pinfunction "RV_25") (pintype "passive"))
      (node (ref "SW7") (pin "26") (pinfunction "RV_26") (pintype "passive"))
    )
    (net (code "59") (name "/RV1_8") (class "Default")
      (node (ref "SW8") (pin "25") (pinfunction "RV_25") (pintype "passive"))
      (node (ref "SW8") (pin "26") (pinfunction "RV_26") (pintype "passive"))
    )
    (net (code "60") (name "/RV2_1") (class "Default")
      (node (ref "SW9") (pin "25") (pinfunction "RV_25") (pintype "passive"))
      (node (ref "SW9") (pin "26") (pinfunction "RV_26") (pintype "passive"))
    )
    (net (code "61") (name "/RV2_2") (class "Default")
      (node (ref "SW10") (pin "25") (pinfunction "RV_25") (pintype "passive"))
      (node (ref "SW10") (pin "26") (pinfunction "RV_26") (pintype "passive"))
    )
    (net (code "62") (name "/RV2_3") (class "Default")
      (node (ref "SW11") (pin "25") (pinfunction "RV_25") (pintype "passive"))
      (node (ref "SW11") (pin "26") (pinfunction "RV_26") (pintype "passive"))
    )
    (net (code "63") (name "/RV2_4") (class "Default")
      (node (ref "SW12") (pin "25") (pinfunction "RV_25") (pintype "passive"))
      (node (ref "SW12") (pin "26") (pinfunction "RV_26") (pintype "passive"))
    )
    (net (code "64") (name "/RV2_5") (class "Default")
      (node (ref "SW13") (pin "25") (pinfunction "RV_25") (pintype "passive"))
      (node (ref "SW13") (pin "26") (pinfunction "RV_26") (pintype "passive"))
    )
    (net (code "65") (name "/RV2_6") (class "Default")
      (node (ref "SW14") (pin "25") (pinfunction "RV_25") (pintype "passive"))
      (node (ref "SW14") (pin "26") (pinfunction "RV_26") (pintype "passive"))
    )
    (net (code "66") (name "/RV2_7") (class "Default")
      (node (ref "SW15") (pin "25") (pinfunction "RV_25") (pintype "passive"))
      (node (ref "SW15") (pin "26") (pinfunction "RV_26") (pintype "passive"))
    )
    (net (code "67") (name "/RV2_8") (class "Default")
      (node (ref "SW16") (pin "25") (pinfunction "RV_25") (pintype "passive"))
      (node (ref "SW16") (pin "26") (pinfunction "RV_26") (pintype "passive"))
    )
    (net (code "68") (name "/RV3_1") (class "Default")
      (node (ref "SW17") (pin "25") (pinfunction "RV_25") (pintype "passive"))
      (node (ref "SW17") (pin "26") (pinfunction "RV_26") (pintype "passive"))
    )
    (net (code "69") (name "/RV3_2") (class "Default")
      (node (ref "SW18") (pin "25") (pinfunction "RV_25") (pintype "passive"))
      (node (ref "SW18") (pin "26") (pinfunction "RV_26") (pintype "passive"))
    )
    (net (code "70") (name "/RV3_3") (class "Default")
      (node (ref "SW19") (pin "25") (pinfunction "RV_25") (pintype "passive"))
      (node (ref "SW19") (pin "26") (pinfunction "RV_26") (pintype "passive"))
    )
    (net (code "71") (name "/RV3_4") (class "Default")
      (node (ref "SW20") (pin "25") (pinfunction "RV_25") (pintype "passive"))
      (node (ref "SW20") (pin "26") (pinfunction "RV_26") (pintype "passive"))
    )
    (net (code "72") (name "/RV3_5") (class "Default")
      (node (ref "SW21") (pin "25") (pinfunction "RV_25") (pintype "passive"))
      (node (ref "SW21") (pin "26") (pinfunction "RV_26") (pintype "passive"))
    )
    (net (code "73") (name "/RV3_6") (class "Default")
      (node (ref "SW22") (pin "25") (pinfunction "RV_25") (pintype "passive"))
      (node (ref "SW22") (pin "26") (pinfunction "RV_26") (pintype "passive"))
    )
    (net (code "74") (name "/RV3_7") (class "Default")
      (node (ref "SW23") (pin "25") (pinfunction "RV_25") (pintype "passive"))
      (node (ref "SW23") (pin "26") (pinfunction "RV_26") (pintype "passive"))
    )
    (net (code "75") (name "/RV3_8") (class "Default")
      (node (ref "SW24") (pin "25") (pinfunction "RV_25") (pintype "passive"))
      (node (ref "SW24") (pin "26") (pinfunction "RV_26") (pintype "passive"))
    )
    (net (code "76") (name "DGND") (class "Default")
      (node (ref "SW1") (pin "27") (pinfunction "DGND_27") (pintype "passive"))
      (node (ref "SW1") (pin "28") (pinfunction "DGND_28") (pintype "passive"))
      (node (ref "SW10") (pin "27") (pinfunction "DGND_27") (pintype "passive"))
      (node (ref "SW10") (pin "28") (pinfunction "DGND_28") (pintype "passive"))
      (node (ref "SW11") (pin "27") (pinfunction "DGND_27") (pintype "passive"))
      (node (ref "SW11") (pin "28") (pinfunction "DGND_28") (pintype "passive"))
      (node (ref "SW12") (pin "27") (pinfunction "DGND_27") (pintype "passive"))
      (node (ref "SW12") (pin "28") (pinfunction "DGND_28") (pintype "passive"))
      (node (ref "SW13") (pin "27") (pinfunction "DGND_27") (pintype "passive"))
      (node (ref "SW13") (pin "28") (pinfunction "DGND_28") (pintype "passive"))
      (node (ref "SW14") (pin "27") (pinfunction "DGND_27") (pintype "passive"))
      (node (ref "SW14") (pin "28") (pinfunction "DGND_28") (pintype "passive"))
      (node (ref "SW15") (pin "27") (pinfunction "DGND_27") (pintype "passive"))
      (node (ref "SW15") (pin "28") (pinfunction "DGND_28") (pintype "passive"))
      (node (ref "SW16") (pin "27") (pinfunction "DGND_27") (pintype "passive"))
      (node (ref "SW16") (pin "28") (pinfunction "DGND_28") (pintype "passive"))
      (node (ref "SW17") (pin "27") (pinfunction "DGND_27") (pintype "passive"))
      (node (ref "SW17") (pin "28") (pinfunction "DGND_28") (pintype "passive"))
      (node (ref "SW18") (pin "27") (pinfunction "DGND_27") (pintype "passive"))
      (node (ref "SW18") (pin "28") (pinfunction "DGND_28") (pintype "passive"))
      (node (ref "SW19") (pin "27") (pinfunction "DGND_27") (pintype "passive"))
      (node (ref "SW19") (pin "28") (pinfunction "DGND_28") (pintype "passive"))
      (node (ref "SW2") (pin "27") (pinfunction "DGND_27") (pintype "passive"))
      (node (ref "SW2") (pin "28") (pinfunction "DGND_28") (pintype "passive"))
      (node (ref "SW20") (pin "27") (pinfunction "DGND_27") (pintype "passive"))
      (node (ref "SW20") (pin "28") (pinfunction "DGND_28") (pintype "passive"))
      (node (ref "SW21") (pin "27") (pinfunction "DGND_27") (pintype "passive"))
      (node (ref "SW21") (pin "28") (pinfunction "DGND_28") (pintype "passive"))
      (node (ref "SW22") (pin "27") (pinfunction "DGND_27") (pintype "passive"))
      (node (ref "SW22") (pin "28") (pinfunction "DGND_28") (pintype "passive"))
      (node (ref "SW23") (pin "27") (pinfunction "DGND_27") (pintype "passive"))
      (node (ref "SW23") (pin "28") (pinfunction "DGND_28") (pintype "passive"))
      (node (ref "SW24") (pin "27") (pinfunction "DGND_27") (pintype "passive"))
      (node (ref "SW24") (pin "28") (pinfunction "DGND_28") (pintype "passive"))
      (node (ref "SW3") (pin "27") (pinfunction "DGND_27") (pintype "passive"))
      (node (ref "SW3") (pin "28") (pinfunction "DGND_28") (pintype "passive"))
      (node (ref "SW4") (pin "27") (pinfunction "DGND_27") (pintype "passive"))
      (node (ref "SW4") (pin "28") (pinfunction "DGND_28") (pintype "passive"))
      (node (ref "SW5") (pin "27") (pinfunction "DGND_27") (pintype "passive"))
      (node (ref "SW5") (pin "28") (pinfunction "DGND_28") (pintype "passive"))
      (node (ref "SW6") (pin "27") (pinfunction "DGND_27") (pintype "passive"))
      (node (ref "SW6") (pin "28") (pinfunction "DGND_28") (pintype "passive"))
      (node (ref "SW7") (pin "27") (pinfunction "DGND_27") (pintype "passive"))
      (node (ref "SW7") (pin "28") (pinfunction "DGND_28") (pintype "passive"))
      (node (ref "SW8") (pin "27") (pinfunction "DGND_27") (pintype "passive"))
      (node (ref "SW8") (pin "28") (pinfunction "DGND_28") (pintype "passive"))
      (node (ref "SW9") (pin "27") (pinfunction "DGND_27") (pintype "passive"))
      (node (ref "SW9") (pin "28") (pinfunction "DGND_28") (pintype "passive"))
    )
    (net (code "77") (name "GND") (class "Default")
      (node (ref "SW1") (pin "10") (pinfunction "GND_10") (pintype "passive"))
      (node (ref "SW1") (pin "11") (pinfunction "GND_11") (pintype "passive"))
      (node (ref "SW1") (pin "12") (pinfunction "GND_12") (pintype "passive"))
      (node (ref "SW1") (pin "13") (pinfunction "GND_13") (pintype "passive"))
      (node (ref "SW1") (pin "14") (pinfunction "GND_14") (pintype "passive"))
      (node (ref "SW1") (pin "15") (pinfunction "GND_15") (pintype "passive"))
      (node (ref "SW1") (pin "16") (pinfunction "GND_16") (pintype "passive"))
      (node (ref "SW1") (pin "9") (pinfunction "GND_9") (pintype "passive"))
      (node (ref "SW10") (pin "10") (pinfunction "GND_10") (pintype "passive"))
      (node (ref "SW10") (pin "11") (pinfunction "GND_11") (pintype "passive"))
      (node (ref "SW10") (pin "12") (pinfunction "GND_12") (pintype "passive"))
      (node (ref "SW10") (pin "13") (pinfunction "GND_13") (pintype "passive"))
      (node (ref "SW10") (pin "14") (pinfunction "GND_14") (pintype "passive"))
      (node (ref "SW10") (pin "15") (pinfunction "GND_15") (pintype "passive"))
      (node (ref "SW10") (pin "16") (pinfunction "GND_16") (pintype "passive"))
      (node (ref "SW10") (pin "9") (pinfunction "GND_9") (pintype "passive"))
      (node (ref "SW11") (pin "10") (pinfunction "GND_10") (pintype "passive"))
      (node (ref "SW11") (pin "11") (pinfunction "GND_11") (pintype "passive"))
      (node (ref "SW11") (pin "12") (pinfunction "GND_12") (pintype "passive"))
      (node (ref "SW11") (pin "13") (pinfunction "GND_13") (pintype "passive"))
      (node (ref "SW11") (pin "14") (pinfunction "GND_14") (pintype "passive"))
      (node (ref "SW11") (pin "15") (pinfunction "GND_15") (pintype "passive"))
      (node (ref "SW11") (pin "16") (pinfunction "GND_16") (pintype "passive"))
      (node (ref "SW11") (pin "9") (pinfunction "GND_9") (pintype "passive"))
      (node (ref "SW12") (pin "10") (pinfunction "GND_10") (pintype "passive"))
      (node (ref "SW12") (pin "11") (pinfunction "GND_11") (pintype "passive"))
      (node (ref "SW12") (pin "12") (pinfunction "GND_12") (pintype "passive"))
      (node (ref "SW12") (pin "13") (pinfunction "GND_13") (pintype "passive"))
      (node (ref "SW12") (pin "14") (pinfunction "GND_14") (pintype "passive"))
      (node (ref "SW12") (pin "15") (pinfunction "GND_15") (pintype "passive"))
      (node (ref "SW12") (pin "16") (pinfunction "GND_16") (pintype "passive"))
      (node (ref "SW12") (pin "9") (pinfunction "GND_9") (pintype "passive"))
      (node (ref "SW13") (pin "10") (pinfunction "GND_10") (pintype "passive"))
      (node (ref "SW13") (pin "11") (pinfunction "GND_11") (pintype "passive"))
      (node (ref "SW13") (pin "12") (pinfunction "GND_12") (pintype "passive"))
      (node (ref "SW13") (pin "13") (pinfunction "GND_13") (pintype "passive"))
      (node (ref "SW13") (pin "14") (pinfunction "GND_14") (pintype "passive"))
      (node (ref "SW13") (pin "15") (pinfunction "GND_15") (pintype "passive"))
      (node (ref "SW13") (pin "16") (pinfunction "GND_16") (pintype "passive"))
      (node (ref "SW13") (pin "9") (pinfunction "GND_9") (pintype "passive"))
      (node (ref "SW14") (pin "10") (pinfunction "GND_10") (pintype "passive"))
      (node (ref "SW14") (pin "11") (pinfunction "GND_11") (pintype "passive"))
      (node (ref "SW14") (pin "12") (pinfunction "GND_12") (pintype "passive"))
      (node (ref "SW14") (pin "13") (pinfunction "GND_13") (pintype "passive"))
      (node (ref "SW14") (pin "14") (pinfunction "GND_14") (pintype "passive"))
      (node (ref "SW14") (pin "15") (pinfunction "GND_15") (pintype "passive"))
      (node (ref "SW14") (pin "16") (pinfunction "GND_16") (pintype "passive"))
      (node (ref "SW14") (pin "9") (pinfunction "GND_9") (pintype "passive"))
      (node (ref "SW15") (pin "10") (pinfunction "GND_10") (pintype "passive"))
      (node (ref "SW15") (pin "11") (pinfunction "GND_11") (pintype "passive"))
      (node (ref "SW15") (pin "12") (pinfunction "GND_12") (pintype "passive"))
      (node (ref "SW15") (pin "13") (pinfunction "GND_13") (pintype "passive"))
      (node (ref "SW15") (pin "14") (pinfunction "GND_14") (pintype "passive"))
      (node (ref "SW15") (pin "15") (pinfunction "GND_15") (pintype "passive"))
      (node (ref "SW15") (pin "16") (pinfunction "GND_16") (pintype "passive"))
      (node (ref "SW15") (pin "9") (pinfunction "GND_9") (pintype "passive"))
      (node (ref "SW16") (pin "10") (pinfunction "GND_10") (pintype "passive"))
      (node (ref "SW16") (pin "11") (pinfunction "GND_11") (pintype "passive"))
      (node (ref "SW16") (pin "12") (pinfunction "GND_12") (pintype "passive"))
      (node (ref "SW16") (pin "13") (pinfunction "GND_13") (pintype "passive"))
      (node (ref "SW16") (pin "14") (pinfunction "GND_14") (pintype "passive"))
      (node (ref "SW16") (pin "15") (pinfunction "GND_15") (pintype "passive"))
      (node (ref "SW16") (pin "16") (pinfunction "GND_16") (pintype "passive"))
      (node (ref "SW16") (pin "9") (pinfunction "GND_9") (pintype "passive"))
      (node (ref "SW17") (pin "10") (pinfunction "GND_10") (pintype "passive"))
      (node (ref "SW17") (pin "11") (pinfunction "GND_11") (pintype "passive"))
      (node (ref "SW17") (pin "12") (pinfunction "GND_12") (pintype "passive"))
      (node (ref "SW17") (pin "13") (pinfunction "GND_13") (pintype "passive"))
      (node (ref "SW17") (pin "14") (pinfunction "GND_14") (pintype "passive"))
      (node (ref "SW17") (pin "15") (pinfunction "GND_15") (pintype "passive"))
      (node (ref "SW17") (pin "16") (pinfunction "GND_16") (pintype "passive"))
      (node (ref "SW17") (pin "9") (pinfunction "GND_9") (pintype "passive"))
      (node (ref "SW18") (pin "10") (pinfunction "GND_10") (pintype "passive"))
      (node (ref "SW18") (pin "11") (pinfunction "GND_11") (pintype "passive"))
      (node (ref "SW18") (pin "12") (pinfunction "GND_12") (pintype "passive"))
      (node (ref "SW18") (pin "13") (pinfunction "GND_13") (pintype "passive"))
      (node (ref "SW18") (pin "14") (pinfunction "GND_14") (pintype "passive"))
      (node (ref "SW18") (pin "15") (pinfunction "GND_15") (pintype "passive"))
      (node (ref "SW18") (pin "16") (pinfunction "GND_16") (pintype "passive"))
      (node (ref "SW18") (pin "9") (pinfunction "GND_9") (pintype "passive"))
      (node (ref "SW19") (pin "10") (pinfunction "GND_10") (pintype "passive"))
      (node (ref "SW19") (pin "11") (pinfunction "GND_11") (pintype "passive"))
      (node (ref "SW19") (pin "12") (pinfunction "GND_12") (pintype "passive"))
      (node (ref "SW19") (pin "13") (pinfunction "GND_13") (pintype "passive"))
      (node (ref "SW19") (pin "14") (pinfunction "GND_14") (pintype "passive"))
      (node (ref "SW19") (pin "15") (pinfunction "GND_15") (pintype "passive"))
      (node (ref "SW19") (pin "16") (pinfunction "GND_16") (pintype "passive"))
      (node (ref "SW19") (pin "9") (pinfunction "GND_9") (pintype "passive"))
      (node (ref "SW2") (pin "10") (pinfunction "GND_10") (pintype "passive"))
      (node (ref "SW2") (pin "11") (pinfunction "GND_11") (pintype "passive"))
      (node (ref "SW2") (pin "12") (pinfunction "GND_12") (pintype "passive"))
      (node (ref "SW2") (pin "13") (pinfunction "GND_13") (pintype "passive"))
      (node (ref "SW2") (pin "14") (pinfunction "GND_14") (pintype "passive"))
      (node (ref "SW2") (pin "15") (pinfunction "GND_15") (pintype "passive"))
      (node (ref "SW2") (pin "16") (pinfunction "GND_16") (pintype "passive"))
      (node (ref "SW2") (pin "9") (pinfunction "GND_9") (pintype "passive"))
      (node (ref "SW20") (pin "10") (pinfunction "GND_10") (pintype "passive"))
      (node (ref "SW20") (pin "11") (pinfunction "GND_11") (pintype "passive"))
      (node (ref "SW20") (pin "12") (pinfunction "GND_12") (pintype "passive"))
      (node (ref "SW20") (pin "13") (pinfunction "GND_13") (pintype "passive"))
      (node (ref "SW20") (pin "14") (pinfunction "GND_14") (pintype "passive"))
      (node (ref "SW20") (pin "15") (pinfunction "GND_15") (pintype "passive"))
      (node (ref "SW20") (pin "16") (pinfunction "GND_16") (pintype "passive"))
      (node (ref "SW20") (pin "9") (pinfunction "GND_9") (pintype "passive"))
      (node (ref "SW21") (pin "10") (pinfunction "GND_10") (pintype "passive"))
      (node (ref "SW21") (pin "11") (pinfunction "GND_11") (pintype "passive"))
      (node (ref "SW21") (pin "12") (pinfunction "GND_12") (pintype "passive"))
      (node (ref "SW21") (pin "13") (pinfunction "GND_13") (pintype "passive"))
      (node (ref "SW21") (pin "14") (pinfunction "GND_14") (pintype "passive"))
      (node (ref "SW21") (pin "15") (pinfunction "GND_15") (pintype "passive"))
      (node (ref "SW21") (pin "16") (pinfunction "GND_16") (pintype "passive"))
      (node (ref "SW21") (pin "9") (pinfunction "GND_9") (pintype "passive"))
      (node (ref "SW22") (pin "10") (pinfunction "GND_10") (pintype "passive"))
      (node (ref "SW22") (pin "11") (pinfunction "GND_11") (pintype "passive"))
      (node (ref "SW22") (pin "12") (pinfunction "GND_12") (pintype "passive"))
      (node (ref "SW22") (pin "13") (pinfunction "GND_13") (pintype "passive"))
      (node (ref "SW22") (pin "14") (pinfunction "GND_14") (pintype "passive"))
      (node (ref "SW22") (pin "15") (pinfunction "GND_15") (pintype "passive"))
      (node (ref "SW22") (pin "16") (pinfunction "GND_16") (pintype "passive"))
      (node (ref "SW22") (pin "9") (pinfunction "GND_9") (pintype "passive"))
      (node (ref "SW23") (pin "10") (pinfunction "GND_10") (pintype "passive"))
      (node (ref "SW23") (pin "11") (pinfunction "GND_11") (pintype "passive"))
      (node (ref "SW23") (pin "12") (pinfunction "GND_12") (pintype "passive"))
      (node (ref "SW23") (pin "13") (pinfunction "GND_13") (pintype "passive"))
      (node (ref "SW23") (pin "14") (pinfunction "GND_14") (pintype "passive"))
      (node (ref "SW23") (pin "15") (pinfunction "GND_15") (pintype "passive"))
      (node (ref "SW23") (pin "16") (pinfunction "GND_16") (pintype "passive"))
      (node (ref "SW23") (pin "9") (pinfunction "GND_9") (pintype "passive"))
      (node (ref "SW24") (pin "10") (pinfunction "GND_10") (pintype "passive"))
      (node (ref "SW24") (pin "11") (pinfunction "GND_11") (pintype "passive"))
      (node (ref "SW24") (pin "12") (pinfunction "GND_12") (pintype "passive"))
      (node (ref "SW24") (pin "13") (pinfunction "GND_13") (pintype "passive"))
      (node (ref "SW24") (pin "14") (pinfunction "GND_14") (pintype "passive"))
      (node (ref "SW24") (pin "15") (pinfunction "GND_15") (pintype "passive"))
      (node (ref "SW24") (pin "16") (pinfunction "GND_16") (pintype "passive"))
      (node (ref "SW24") (pin "9") (pinfunction "GND_9") (pintype "passive"))
      (node (ref "SW3") (pin "10") (pinfunction "GND_10") (pintype "passive"))
      (node (ref "SW3") (pin "11") (pinfunction "GND_11") (pintype "passive"))
      (node (ref "SW3") (pin "12") (pinfunction "GND_12") (pintype "passive"))
      (node (ref "SW3") (pin "13") (pinfunction "GND_13") (pintype "passive"))
      (node (ref "SW3") (pin "14") (pinfunction "GND_14") (pintype "passive"))
      (node (ref "SW3") (pin "15") (pinfunction "GND_15") (pintype "passive"))
      (node (ref "SW3") (pin "16") (pinfunction "GND_16") (pintype "passive"))
      (node (ref "SW3") (pin "9") (pinfunction "GND_9") (pintype "passive"))
      (node (ref "SW4") (pin "10") (pinfunction "GND_10") (pintype "passive"))
      (node (ref "SW4") (pin "11") (pinfunction "GND_11") (pintype "passive"))
      (node (ref "SW4") (pin "12") (pinfunction "GND_12") (pintype "passive"))
      (node (ref "SW4") (pin "13") (pinfunction "GND_13") (pintype "passive"))
      (node (ref "SW4") (pin "14") (pinfunction "GND_14") (pintype "passive"))
      (node (ref "SW4") (pin "15") (pinfunction "GND_15") (pintype "passive"))
      (node (ref "SW4") (pin "16") (pinfunction "GND_16") (pintype "passive"))
      (node (ref "SW4") (pin "9") (pinfunction "GND_9") (pintype "passive"))
      (node (ref "SW5") (pin "10") (pinfunction "GND_10") (pintype "passive"))
      (node (ref "SW5") (pin "11") (pinfunction "GND_11") (pintype "passive"))
      (node (ref "SW5") (pin "12") (pinfunction "GND_12") (pintype "passive"))
      (node (ref "SW5") (pin "13") (pinfunction "GND_13") (pintype "passive"))
      (node (ref "SW5") (pin "14") (pinfunction "GND_14") (pintype "passive"))
      (node (ref "SW5") (pin "15") (pinfunction "GND_15") (pintype "passive"))
      (node (ref "SW5") (pin "16") (pinfunction "GND_16") (pintype "passive"))
      (node (ref "SW5") (pin "9") (pinfunction "GND_9") (pintype "passive"))
      (node (ref "SW6") (pin "10") (pinfunction "GND_10") (pintype "passive"))
      (node (ref "SW6") (pin "11") (pinfunction "GND_11") (pintype "passive"))
      (node (ref "SW6") (pin "12") (pinfunction "GND_12") (pintype "passive"))
      (node (ref "SW6") (pin "13") (pinfunction "GND_13") (pintype "passive"))
      (node (ref "SW6") (pin "14") (pinfunction "GND_14") (pintype "passive"))
      (node (ref "SW6") (pin "15") (pinfunction "GND_15") (pintype "passive"))
      (node (ref "SW6") (pin "16") (pinfunction "GND_16") (pintype "passive"))
      (node (ref "SW6") (pin "9") (pinfunction "GND_9") (pintype "passive"))
      (node (ref "SW7") (pin "10") (pinfunction "GND_10") (pintype "passive"))
      (node (ref "SW7") (pin "11") (pinfunction "GND_11") (pintype "passive"))
      (node (ref "SW7") (pin "12") (pinfunction "GND_12") (pintype "passive"))
      (node (ref "SW7") (pin "13") (pinfunction "GND_13") (pintype "passive"))
      (node (ref "SW7") (pin "14") (pinfunction "GND_14") (pintype "passive"))
      (node (ref "SW7") (pin "15") (pinfunction "GND_15") (pintype "passive"))
      (node (ref "SW7") (pin "16") (pinfunction "GND_16") (pintype "passive"))
      (node (ref "SW7") (pin "9") (pinfunction "GND_9") (pintype "passive"))
      (node (ref "SW8") (pin "10") (pinfunction "GND_10") (pintype "passive"))
      (node (ref "SW8") (pin "11") (pinfunction "GND_11") (pintype "passive"))
      (node (ref "SW8") (pin "12") (pinfunction "GND_12") (pintype "passive"))
      (node (ref "SW8") (pin "13") (pinfunction "GND_13") (pintype "passive"))
      (node (ref "SW8") (pin "14") (pinfunction "GND_14") (pintype "passive"))
      (node (ref "SW8") (pin "15") (pinfunction "GND_15") (pintype "passive"))
      (node (ref "SW8") (pin "16") (pinfunction "GND_16") (pintype "passive"))
      (node (ref "SW8") (pin "9") (pinfunction "GND_9") (pintype "passive"))
      (node (ref "SW9") (pin "10") (pinfunction "GND_10") (pintype "passive"))
      (node (ref "SW9") (pin "11") (pinfunction "GND_11") (pintype "passive"))
      (node (ref "SW9") (pin "12") (pinfunction "GND_12") (pintype "passive"))
      (node (ref "SW9") (pin "13") (pinfunction "GND_13") (pintype "passive"))
      (node (ref "SW9") (pin "14") (pinfunction "GND_14") (pintype "passive"))
      (node (ref "SW9") (pin "15") (pinfunction "GND_15") (pintype "passive"))
      (node (ref "SW9") (pin "16") (pinfunction "GND_16") (pintype "passive"))
      (node (ref "SW9") (pin "9") (pinfunction "GND_9") (pintype "passive"))
    )
  )
)
